# Keyboard.net
KiCad netlist of a schematic drawn in EasyEDA Pro
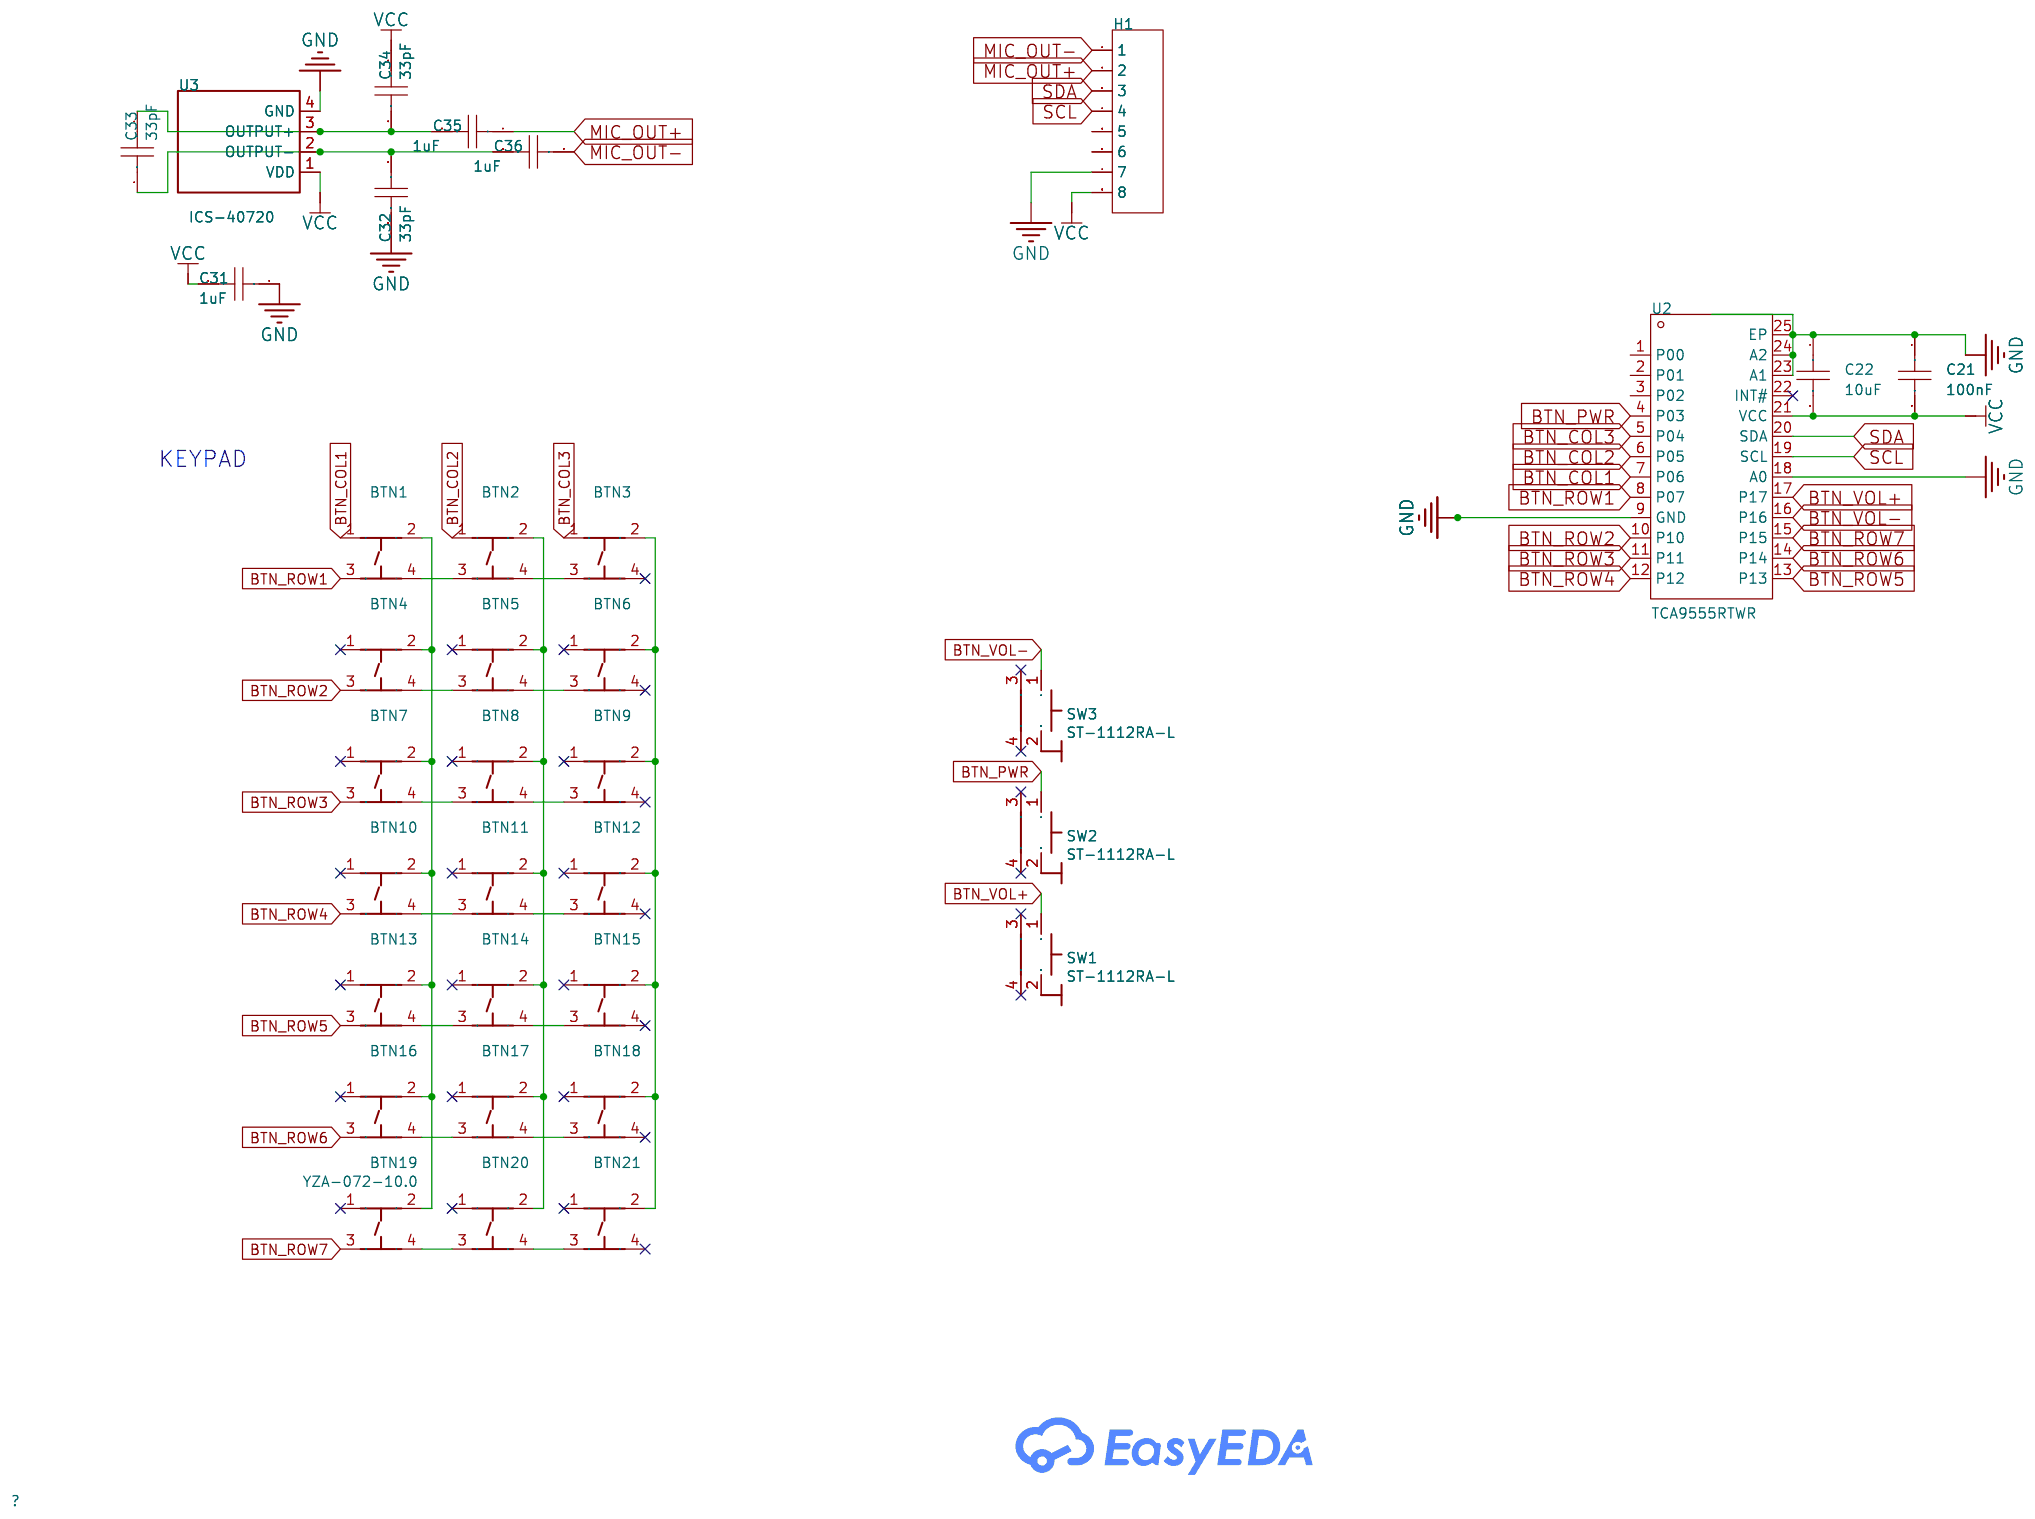
[diagram p0: schematic sheet]

(export (version "E")
  (design (tool "Eeschema 10.0.6"))
  (components
    (comp (ref "BTN1")
      (value "YZA-072-10.0")
      (footprint "easyedapro:SW-SMD_4P-L6.0-W6.0-P4.5-LS9.0-YZA-072-10.0")
      (fields (field (name "Manufacturer") "YIZHI(逸致)") (field (name "Contributor") "lcsc"))
      (libsource (lib "easyedapro") (part "YZA-072-10.0"))
    )
    (comp (ref "BTN2")
      (value "YZA-072-10.0")
      (footprint "easyedapro:SW-SMD_4P-L6.0-W6.0-P4.5-LS9.0-YZA-072-10.0")
      (fields (field (name "Manufacturer") "YIZHI(逸致)") (field (name "Contributor") "lcsc"))
      (libsource (lib "easyedapro") (part "YZA-072-10.0"))
    )
    (comp (ref "BTN3")
      (value "YZA-072-10.0")
      (footprint "easyedapro:SW-SMD_4P-L6.0-W6.0-P4.5-LS9.0-YZA-072-10.0")
      (fields (field (name "Manufacturer") "YIZHI(逸致)") (field (name "Contributor") "lcsc"))
      (libsource (lib "easyedapro") (part "YZA-072-10.0"))
    )
    (comp (ref "BTN4")
      (value "YZA-072-10.0")
      (footprint "easyedapro:SW-SMD_4P-L6.0-W6.0-P4.5-LS9.0-YZA-072-10.0")
      (fields (field (name "Manufacturer") "YIZHI(逸致)") (field (name "Contributor") "lcsc"))
      (libsource (lib "easyedapro") (part "YZA-072-10.0"))
    )
    (comp (ref "BTN5")
      (value "YZA-072-10.0")
      (footprint "easyedapro:SW-SMD_4P-L6.0-W6.0-P4.5-LS9.0-YZA-072-10.0")
      (fields (field (name "Manufacturer") "YIZHI(逸致)") (field (name "Contributor") "lcsc"))
      (libsource (lib "easyedapro") (part "YZA-072-10.0"))
    )
    (comp (ref "BTN6")
      (value "YZA-072-10.0")
      (footprint "easyedapro:SW-SMD_4P-L6.0-W6.0-P4.5-LS9.0-YZA-072-10.0")
      (fields (field (name "Manufacturer") "YIZHI(逸致)") (field (name "Contributor") "lcsc"))
      (libsource (lib "easyedapro") (part "YZA-072-10.0"))
    )
    (comp (ref "BTN7")
      (value "YZA-072-10.0")
      (footprint "easyedapro:SW-SMD_4P-L6.0-W6.0-P4.5-LS9.0-YZA-072-10.0")
      (fields (field (name "Manufacturer") "YIZHI(逸致)") (field (name "Contributor") "lcsc"))
      (libsource (lib "easyedapro") (part "YZA-072-10.0"))
    )
    (comp (ref "BTN8")
      (value "YZA-072-10.0")
      (footprint "easyedapro:SW-SMD_4P-L6.0-W6.0-P4.5-LS9.0-YZA-072-10.0")
      (fields (field (name "Manufacturer") "YIZHI(逸致)") (field (name "Contributor") "lcsc"))
      (libsource (lib "easyedapro") (part "YZA-072-10.0"))
    )
    (comp (ref "BTN9")
      (value "YZA-072-10.0")
      (footprint "easyedapro:SW-SMD_4P-L6.0-W6.0-P4.5-LS9.0-YZA-072-10.0")
      (fields (field (name "Manufacturer") "YIZHI(逸致)") (field (name "Contributor") "lcsc"))
      (libsource (lib "easyedapro") (part "YZA-072-10.0"))
    )
    (comp (ref "BTN10")
      (value "YZA-072-10.0")
      (footprint "easyedapro:SW-SMD_4P-L6.0-W6.0-P4.5-LS9.0-YZA-072-10.0")
      (fields (field (name "Manufacturer") "YIZHI(逸致)") (field (name "Contributor") "lcsc"))
      (libsource (lib "easyedapro") (part "YZA-072-10.0"))
    )
    (comp (ref "BTN11")
      (value "YZA-072-10.0")
      (footprint "easyedapro:SW-SMD_4P-L6.0-W6.0-P4.5-LS9.0-YZA-072-10.0")
      (fields (field (name "Manufacturer") "YIZHI(逸致)") (field (name "Contributor") "lcsc"))
      (libsource (lib "easyedapro") (part "YZA-072-10.0"))
    )
    (comp (ref "BTN12")
      (value "YZA-072-10.0")
      (footprint "easyedapro:SW-SMD_4P-L6.0-W6.0-P4.5-LS9.0-YZA-072-10.0")
      (fields (field (name "Manufacturer") "YIZHI(逸致)") (field (name "Contributor") "lcsc"))
      (libsource (lib "easyedapro") (part "YZA-072-10.0"))
    )
    (comp (ref "BTN13")
      (value "YZA-072-10.0")
      (footprint "easyedapro:SW-SMD_4P-L6.0-W6.0-P4.5-LS9.0-YZA-072-10.0")
      (fields (field (name "Manufacturer") "YIZHI(逸致)") (field (name "Contributor") "lcsc"))
      (libsource (lib "easyedapro") (part "YZA-072-10.0"))
    )
    (comp (ref "BTN14")
      (value "YZA-072-10.0")
      (footprint "easyedapro:SW-SMD_4P-L6.0-W6.0-P4.5-LS9.0-YZA-072-10.0")
      (fields (field (name "Manufacturer") "YIZHI(逸致)") (field (name "Contributor") "lcsc"))
      (libsource (lib "easyedapro") (part "YZA-072-10.0"))
    )
    (comp (ref "BTN15")
      (value "YZA-072-10.0")
      (footprint "easyedapro:SW-SMD_4P-L6.0-W6.0-P4.5-LS9.0-YZA-072-10.0")
      (fields (field (name "Manufacturer") "YIZHI(逸致)") (field (name "Contributor") "lcsc"))
      (libsource (lib "easyedapro") (part "YZA-072-10.0"))
    )
    (comp (ref "BTN16")
      (value "YZA-072-10.0")
      (footprint "easyedapro:SW-SMD_4P-L6.0-W6.0-P4.5-LS9.0-YZA-072-10.0")
      (fields (field (name "Manufacturer") "YIZHI(逸致)") (field (name "Contributor") "lcsc"))
      (libsource (lib "easyedapro") (part "YZA-072-10.0"))
    )
    (comp (ref "BTN17")
      (value "YZA-072-10.0")
      (footprint "easyedapro:SW-SMD_4P-L6.0-W6.0-P4.5-LS9.0-YZA-072-10.0")
      (fields (field (name "Manufacturer") "YIZHI(逸致)") (field (name "Contributor") "lcsc"))
      (libsource (lib "easyedapro") (part "YZA-072-10.0"))
    )
    (comp (ref "BTN18")
      (value "YZA-072-10.0")
      (footprint "easyedapro:SW-SMD_4P-L6.0-W6.0-P4.5-LS9.0-YZA-072-10.0")
      (fields (field (name "Manufacturer") "YIZHI(逸致)") (field (name "Contributor") "lcsc"))
      (libsource (lib "easyedapro") (part "YZA-072-10.0"))
    )
    (comp (ref "BTN19")
      (value "YZA-072-10.0")
      (footprint "easyedapro:SW-SMD_4P-L6.0-W6.0-P4.5-LS9.0-YZA-072-10.0")
      (fields (field (name "Manufacturer") "YIZHI(逸致)") (field (name "Contributor") "lcsc"))
      (libsource (lib "easyedapro") (part "YZA-072-10.0"))
    )
    (comp (ref "BTN20")
      (value "YZA-072-10.0")
      (footprint "easyedapro:SW-SMD_4P-L6.0-W6.0-P4.5-LS9.0-YZA-072-10.0")
      (fields (field (name "Manufacturer") "YIZHI(逸致)") (field (name "Contributor") "lcsc"))
      (libsource (lib "easyedapro") (part "YZA-072-10.0"))
    )
    (comp (ref "BTN21")
      (value "YZA-072-10.0")
      (footprint "easyedapro:SW-SMD_4P-L6.0-W6.0-P4.5-LS9.0-YZA-072-10.0")
      (fields (field (name "Manufacturer") "YIZHI(逸致)") (field (name "Contributor") "lcsc"))
      (libsource (lib "easyedapro") (part "YZA-072-10.0"))
    )
    (comp (ref "C21")
      (value "100nF")
      (footprint "easyedapro:C0603")
      (libsource (lib "easyedapro") (part "CAP"))
    )
    (comp (ref "C22")
      (value "10uF")
      (footprint "easyedapro:C0603")
      (libsource (lib "easyedapro") (part "CAP"))
    )
    (comp (ref "C31")
      (value "1uF")
      (footprint "easyedapro:C0603")
      (libsource (lib "easyedapro") (part "CAP"))
    )
    (comp (ref "C32")
      (value "33pF")
      (footprint "easyedapro:C0603")
      (libsource (lib "easyedapro") (part "CAP"))
    )
    (comp (ref "C33")
      (value "33pF")
      (footprint "easyedapro:C0603")
      (libsource (lib "easyedapro") (part "CAP"))
    )
    (comp (ref "C34")
      (value "33pF")
      (footprint "easyedapro:C0603")
      (libsource (lib "easyedapro") (part "CAP"))
    )
    (comp (ref "C35")
      (value "1uF")
      (footprint "easyedapro:C0603")
      (libsource (lib "easyedapro") (part "CAP"))
    )
    (comp (ref "C36")
      (value "1uF")
      (footprint "easyedapro:C0603")
      (libsource (lib "easyedapro") (part "CAP"))
    )
    (comp (ref "H1")
      (value "~")
      (footprint "easyedapro:HDR-TH_8P-P2.54-V-M")
      (libsource (lib "easyedapro") (part "Header-Male-2.54_1x8"))
    )
    (comp (ref "SW1")
      (value "ST-1112RA-L")
      (footprint "easyedapro:SW-SMD_ST-1112RA-L")
      (fields (field (name "Manufacturer") "RISHENG(日昇)") (field (name "Contributor") "LCSC"))
      (libsource (lib "easyedapro") (part "ST-1112RA-L"))
    )
    (comp (ref "SW2")
      (value "ST-1112RA-L")
      (footprint "easyedapro:SW-SMD_ST-1112RA-L")
      (fields (field (name "Manufacturer") "RISHENG(日昇)") (field (name "Contributor") "LCSC"))
      (libsource (lib "easyedapro") (part "ST-1112RA-L"))
    )
    (comp (ref "SW3")
      (value "ST-1112RA-L")
      (footprint "easyedapro:SW-SMD_ST-1112RA-L")
      (fields (field (name "Manufacturer") "RISHENG(日昇)") (field (name "Contributor") "LCSC"))
      (libsource (lib "easyedapro") (part "ST-1112RA-L"))
    )
    (comp (ref "U2")
      (value "TCA9555RTWR")
      (footprint "easyedapro:VFQFPN-24_L4.0-W4.0-P0.50-BL-EP2.8")
      (fields (field (name "Manufacturer") "TI(德州仪器)"))
      (libsource (lib "easyedapro") (part "TCA9555RTWR"))
    )
    (comp (ref "U3")
      (value "ICS-40720")
      (footprint "easyedapro:SMD_4P-P0.88_ICS-40720")
      (fields (field (name "Manufacturer") "TDK InvenSense(应美盛)") (field (name "Contributor") "lcsc"))
      (libsource (lib "easyedapro") (part "ICS-40720"))
    )
  )
  (nets
    (net (code "1") (name "BTN_COL1") (class "Default")
      (node (ref "BTN1") (pin "1") (pinfunction "1_1") (pintype "unspecified"))
      (node (ref "U2") (pin "7") (pinfunction "P06_7") (pintype "unspecified"))
    )
    (net (code "2") (name "BTN_COL2") (class "Default")
      (node (ref "BTN2") (pin "1") (pinfunction "1_1") (pintype "unspecified"))
      (node (ref "U2") (pin "6") (pinfunction "P05_6") (pintype "unspecified"))
    )
    (net (code "3") (name "BTN_COL3") (class "Default")
      (node (ref "BTN3") (pin "1") (pinfunction "1_1") (pintype "unspecified"))
      (node (ref "U2") (pin "5") (pinfunction "P04_5") (pintype "unspecified"))
    )
    (net (code "4") (name "BTN_PWR") (class "Default")
      (node (ref "SW2") (pin "1") (pinfunction "1_1") (pintype "unspecified"))
      (node (ref "U2") (pin "4") (pinfunction "P03_4") (pintype "unspecified"))
    )
    (net (code "5") (name "BTN_ROW1") (class "Default")
      (node (ref "BTN1") (pin "3") (pinfunction "3_3") (pintype "unspecified"))
      (node (ref "U2") (pin "8") (pinfunction "P07_8") (pintype "unspecified"))
    )
    (net (code "6") (name "BTN_ROW2") (class "Default")
      (node (ref "BTN4") (pin "3") (pinfunction "3_3") (pintype "unspecified"))
      (node (ref "U2") (pin "10") (pinfunction "P10_10") (pintype "unspecified"))
    )
    (net (code "7") (name "BTN_ROW3") (class "Default")
      (node (ref "BTN7") (pin "3") (pinfunction "3_3") (pintype "unspecified"))
      (node (ref "U2") (pin "11") (pinfunction "P11_11") (pintype "unspecified"))
    )
    (net (code "8") (name "BTN_ROW4") (class "Default")
      (node (ref "BTN10") (pin "3") (pinfunction "3_3") (pintype "unspecified"))
      (node (ref "U2") (pin "12") (pinfunction "P12_12") (pintype "unspecified"))
    )
    (net (code "9") (name "BTN_ROW5") (class "Default")
      (node (ref "BTN13") (pin "3") (pinfunction "3_3") (pintype "unspecified"))
      (node (ref "U2") (pin "13") (pinfunction "P13_13") (pintype "unspecified"))
    )
    (net (code "10") (name "BTN_ROW6") (class "Default")
      (node (ref "BTN16") (pin "3") (pinfunction "3_3") (pintype "unspecified"))
      (node (ref "U2") (pin "14") (pinfunction "P14_14") (pintype "unspecified"))
    )
    (net (code "11") (name "BTN_ROW7") (class "Default")
      (node (ref "BTN19") (pin "3") (pinfunction "3_3") (pintype "unspecified"))
      (node (ref "U2") (pin "15") (pinfunction "P15_15") (pintype "unspecified"))
    )
    (net (code "12") (name "BTN_VOL+") (class "Default")
      (node (ref "SW1") (pin "1") (pinfunction "1_1") (pintype "unspecified"))
      (node (ref "U2") (pin "17") (pinfunction "P17_17") (pintype "unspecified"))
    )
    (net (code "13") (name "BTN_VOL-") (class "Default")
      (node (ref "SW3") (pin "1") (pinfunction "1_1") (pintype "unspecified"))
      (node (ref "U2") (pin "16") (pinfunction "P16_16") (pintype "unspecified"))
    )
    (net (code "14") (name "GND") (class "Default")
      (node (ref "C21") (pin "1") (pinfunction "1_1") (pintype "input"))
      (node (ref "C22") (pin "1") (pinfunction "1_1") (pintype "input"))
      (node (ref "C31") (pin "1") (pinfunction "1_1") (pintype "input"))
      (node (ref "C32") (pin "2") (pinfunction "2_2") (pintype "input"))
      (node (ref "H1") (pin "7") (pinfunction "7_7") (pintype "unspecified"))
      (node (ref "U2") (pin "18") (pinfunction "A0_18") (pintype "unspecified"))
      (node (ref "U2") (pin "23") (pinfunction "A1_23") (pintype "unspecified"))
      (node (ref "U2") (pin "24") (pinfunction "A2_24") (pintype "unspecified"))
      (node (ref "U2") (pin "25") (pinfunction "EP_25") (pintype "unspecified"))
      (node (ref "U2") (pin "9") (pinfunction "GND_9") (pintype "unspecified"))
      (node (ref "U3") (pin "4") (pinfunction "GND_4") (pintype "unspecified"))
    )
    (net (code "15") (name "MIC_OUT+") (class "Default")
      (node (ref "C35") (pin "1") (pinfunction "1_1") (pintype "input"))
      (node (ref "H1") (pin "2") (pinfunction "2_2") (pintype "unspecified"))
    )
    (net (code "16") (name "MIC_OUT-") (class "Default")
      (node (ref "C36") (pin "1") (pinfunction "1_1") (pintype "input"))
      (node (ref "H1") (pin "1") (pinfunction "1_1") (pintype "unspecified"))
    )
    (net (code "17") (name "Net-(BTN1-Pad2)") (class "Default")
      (node (ref "BTN1") (pin "2") (pinfunction "2_2") (pintype "unspecified"))
      (node (ref "BTN10") (pin "2") (pinfunction "2_2") (pintype "unspecified"))
      (node (ref "BTN13") (pin "2") (pinfunction "2_2") (pintype "unspecified"))
      (node (ref "BTN16") (pin "2") (pinfunction "2_2") (pintype "unspecified"))
      (node (ref "BTN19") (pin "2") (pinfunction "2_2") (pintype "unspecified"))
      (node (ref "BTN4") (pin "2") (pinfunction "2_2") (pintype "unspecified"))
      (node (ref "BTN7") (pin "2") (pinfunction "2_2") (pintype "unspecified"))
    )
    (net (code "18") (name "Net-(BTN1-Pad4)") (class "Default")
      (node (ref "BTN1") (pin "4") (pinfunction "4_4") (pintype "unspecified"))
      (node (ref "BTN2") (pin "3") (pinfunction "3_3") (pintype "unspecified"))
    )
    (net (code "19") (name "Net-(BTN2-Pad4)") (class "Default")
      (node (ref "BTN2") (pin "4") (pinfunction "4_4") (pintype "unspecified"))
      (node (ref "BTN3") (pin "3") (pinfunction "3_3") (pintype "unspecified"))
    )
    (net (code "20") (name "Net-(BTN4-Pad4)") (class "Default")
      (node (ref "BTN4") (pin "4") (pinfunction "4_4") (pintype "unspecified"))
      (node (ref "BTN5") (pin "3") (pinfunction "3_3") (pintype "unspecified"))
    )
    (net (code "21") (name "Net-(BTN5-Pad4)") (class "Default")
      (node (ref "BTN5") (pin "4") (pinfunction "4_4") (pintype "unspecified"))
      (node (ref "BTN6") (pin "3") (pinfunction "3_3") (pintype "unspecified"))
    )
    (net (code "22") (name "Net-(BTN7-Pad4)") (class "Default")
      (node (ref "BTN7") (pin "4") (pinfunction "4_4") (pintype "unspecified"))
      (node (ref "BTN8") (pin "3") (pinfunction "3_3") (pintype "unspecified"))
    )
    (net (code "23") (name "Net-(BTN8-Pad4)") (class "Default")
      (node (ref "BTN8") (pin "4") (pinfunction "4_4") (pintype "unspecified"))
      (node (ref "BTN9") (pin "3") (pinfunction "3_3") (pintype "unspecified"))
    )
    (net (code "24") (name "Net-(BTN10-Pad4)") (class "Default")
      (node (ref "BTN10") (pin "4") (pinfunction "4_4") (pintype "unspecified"))
      (node (ref "BTN11") (pin "3") (pinfunction "3_3") (pintype "unspecified"))
    )
    (net (code "25") (name "Net-(BTN11-Pad2)") (class "Default")
      (node (ref "BTN11") (pin "2") (pinfunction "2_2") (pintype "unspecified"))
      (node (ref "BTN14") (pin "2") (pinfunction "2_2") (pintype "unspecified"))
      (node (ref "BTN17") (pin "2") (pinfunction "2_2") (pintype "unspecified"))
      (node (ref "BTN2") (pin "2") (pinfunction "2_2") (pintype "unspecified"))
      (node (ref "BTN20") (pin "2") (pinfunction "2_2") (pintype "unspecified"))
      (node (ref "BTN5") (pin "2") (pinfunction "2_2") (pintype "unspecified"))
      (node (ref "BTN8") (pin "2") (pinfunction "2_2") (pintype "unspecified"))
    )
    (net (code "26") (name "Net-(BTN11-Pad4)") (class "Default")
      (node (ref "BTN11") (pin "4") (pinfunction "4_4") (pintype "unspecified"))
      (node (ref "BTN12") (pin "3") (pinfunction "3_3") (pintype "unspecified"))
    )
    (net (code "27") (name "Net-(BTN12-Pad2)") (class "Default")
      (node (ref "BTN12") (pin "2") (pinfunction "2_2") (pintype "unspecified"))
      (node (ref "BTN15") (pin "2") (pinfunction "2_2") (pintype "unspecified"))
      (node (ref "BTN18") (pin "2") (pinfunction "2_2") (pintype "unspecified"))
      (node (ref "BTN21") (pin "2") (pinfunction "2_2") (pintype "unspecified"))
      (node (ref "BTN3") (pin "2") (pinfunction "2_2") (pintype "unspecified"))
      (node (ref "BTN6") (pin "2") (pinfunction "2_2") (pintype "unspecified"))
      (node (ref "BTN9") (pin "2") (pinfunction "2_2") (pintype "unspecified"))
    )
    (net (code "28") (name "Net-(BTN13-Pad4)") (class "Default")
      (node (ref "BTN13") (pin "4") (pinfunction "4_4") (pintype "unspecified"))
      (node (ref "BTN14") (pin "3") (pinfunction "3_3") (pintype "unspecified"))
    )
    (net (code "29") (name "Net-(BTN14-Pad4)") (class "Default")
      (node (ref "BTN14") (pin "4") (pinfunction "4_4") (pintype "unspecified"))
      (node (ref "BTN15") (pin "3") (pinfunction "3_3") (pintype "unspecified"))
    )
    (net (code "30") (name "Net-(BTN16-Pad4)") (class "Default")
      (node (ref "BTN16") (pin "4") (pinfunction "4_4") (pintype "unspecified"))
      (node (ref "BTN17") (pin "3") (pinfunction "3_3") (pintype "unspecified"))
    )
    (net (code "31") (name "Net-(BTN17-Pad4)") (class "Default")
      (node (ref "BTN17") (pin "4") (pinfunction "4_4") (pintype "unspecified"))
      (node (ref "BTN18") (pin "3") (pinfunction "3_3") (pintype "unspecified"))
    )
    (net (code "32") (name "Net-(BTN19-Pad4)") (class "Default")
      (node (ref "BTN19") (pin "4") (pinfunction "4_4") (pintype "unspecified"))
      (node (ref "BTN20") (pin "3") (pinfunction "3_3") (pintype "unspecified"))
    )
    (net (code "33") (name "Net-(BTN20-Pad4)") (class "Default")
      (node (ref "BTN20") (pin "4") (pinfunction "4_4") (pintype "unspecified"))
      (node (ref "BTN21") (pin "3") (pinfunction "3_3") (pintype "unspecified"))
    )
    (net (code "34") (name "Net-(U3-OUTPUT+)") (class "Default")
      (node (ref "C33") (pin "1") (pinfunction "1_1") (pintype "input"))
      (node (ref "C34") (pin "2") (pinfunction "2_2") (pintype "input"))
      (node (ref "C35") (pin "2") (pinfunction "2_2") (pintype "input"))
      (node (ref "U3") (pin "3") (pinfunction "OUTPUT+_3") (pintype "unspecified"))
    )
    (net (code "35") (name "Net-(U3-OUTPUT−)") (class "Default")
      (node (ref "C32") (pin "1") (pinfunction "1_1") (pintype "input"))
      (node (ref "C33") (pin "2") (pinfunction "2_2") (pintype "input"))
      (node (ref "C36") (pin "2") (pinfunction "2_2") (pintype "input"))
      (node (ref "U3") (pin "2") (pinfunction "OUTPUT−_2") (pintype "unspecified"))
    )
    (net (code "36") (name "SCL") (class "Default")
      (node (ref "H1") (pin "4") (pinfunction "4_4") (pintype "unspecified"))
      (node (ref "U2") (pin "19") (pinfunction "SCL_19") (pintype "unspecified"))
    )
    (net (code "37") (name "SDA") (class "Default")
      (node (ref "H1") (pin "3") (pinfunction "3_3") (pintype "unspecified"))
      (node (ref "U2") (pin "20") (pinfunction "SDA_20") (pintype "unspecified"))
    )
    (net (code "38") (name "VCC") (class "Default")
      (node (ref "C21") (pin "2") (pinfunction "2_2") (pintype "input"))
      (node (ref "C22") (pin "2") (pinfunction "2_2") (pintype "input"))
      (node (ref "C31") (pin "2") (pinfunction "2_2") (pintype "input"))
      (node (ref "C34") (pin "1") (pinfunction "1_1") (pintype "input"))
      (node (ref "H1") (pin "8") (pinfunction "8_8") (pintype "unspecified"))
      (node (ref "SW1") (pin "2") (pinfunction "2_2") (pintype "unspecified"))
      (node (ref "SW2") (pin "2") (pinfunction "2_2") (pintype "unspecified"))
      (node (ref "SW3") (pin "2") (pinfunction "2_2") (pintype "unspecified"))
      (node (ref "U2") (pin "21") (pinfunction "VCC_21") (pintype "unspecified"))
      (node (ref "U3") (pin "1") (pinfunction "VDD_1") (pintype "unspecified"))
    )
    (net (code "39") (name "unconnected-(BTN3-Pad4)") (class "Default")
      (node (ref "BTN3") (pin "4") (pinfunction "4_4") (pintype "unspecified+no_connect"))
    )
    (net (code "40") (name "unconnected-(BTN4-Pad1)") (class "Default")
      (node (ref "BTN4") (pin "1") (pinfunction "1_1") (pintype "unspecified+no_connect"))
    )
    (net (code "41") (name "unconnected-(BTN5-Pad1)") (class "Default")
      (node (ref "BTN5") (pin "1") (pinfunction "1_1") (pintype "unspecified+no_connect"))
    )
    (net (code "42") (name "unconnected-(BTN6-Pad1)") (class "Default")
      (node (ref "BTN6") (pin "1") (pinfunction "1_1") (pintype "unspecified+no_connect"))
    )
    (net (code "43") (name "unconnected-(BTN6-Pad4)") (class "Default")
      (node (ref "BTN6") (pin "4") (pinfunction "4_4") (pintype "unspecified+no_connect"))
    )
    (net (code "44") (name "unconnected-(BTN7-Pad1)") (class "Default")
      (node (ref "BTN7") (pin "1") (pinfunction "1_1") (pintype "unspecified+no_connect"))
    )
    (net (code "45") (name "unconnected-(BTN8-Pad1)") (class "Default")
      (node (ref "BTN8") (pin "1") (pinfunction "1_1") (pintype "unspecified+no_connect"))
    )
    (net (code "46") (name "unconnected-(BTN9-Pad1)") (class "Default")
      (node (ref "BTN9") (pin "1") (pinfunction "1_1") (pintype "unspecified+no_connect"))
    )
    (net (code "47") (name "unconnected-(BTN9-Pad4)") (class "Default")
      (node (ref "BTN9") (pin "4") (pinfunction "4_4") (pintype "unspecified+no_connect"))
    )
    (net (code "48") (name "unconnected-(BTN10-Pad1)") (class "Default")
      (node (ref "BTN10") (pin "1") (pinfunction "1_1") (pintype "unspecified+no_connect"))
    )
    (net (code "49") (name "unconnected-(BTN11-Pad1)") (class "Default")
      (node (ref "BTN11") (pin "1") (pinfunction "1_1") (pintype "unspecified+no_connect"))
    )
    (net (code "50") (name "unconnected-(BTN12-Pad1)") (class "Default")
      (node (ref "BTN12") (pin "1") (pinfunction "1_1") (pintype "unspecified+no_connect"))
    )
    (net (code "51") (name "unconnected-(BTN12-Pad4)") (class "Default")
      (node (ref "BTN12") (pin "4") (pinfunction "4_4") (pintype "unspecified+no_connect"))
    )
    (net (code "52") (name "unconnected-(BTN13-Pad1)") (class "Default")
      (node (ref "BTN13") (pin "1") (pinfunction "1_1") (pintype "unspecified+no_connect"))
    )
    (net (code "53") (name "unconnected-(BTN14-Pad1)") (class "Default")
      (node (ref "BTN14") (pin "1") (pinfunction "1_1") (pintype "unspecified+no_connect"))
    )
    (net (code "54") (name "unconnected-(BTN15-Pad1)") (class "Default")
      (node (ref "BTN15") (pin "1") (pinfunction "1_1") (pintype "unspecified+no_connect"))
    )
    (net (code "55") (name "unconnected-(BTN15-Pad4)") (class "Default")
      (node (ref "BTN15") (pin "4") (pinfunction "4_4") (pintype "unspecified+no_connect"))
    )
    (net (code "56") (name "unconnected-(BTN16-Pad1)") (class "Default")
      (node (ref "BTN16") (pin "1") (pinfunction "1_1") (pintype "unspecified+no_connect"))
    )
    (net (code "57") (name "unconnected-(BTN17-Pad1)") (class "Default")
      (node (ref "BTN17") (pin "1") (pinfunction "1_1") (pintype "unspecified+no_connect"))
    )
    (net (code "58") (name "unconnected-(BTN18-Pad1)") (class "Default")
      (node (ref "BTN18") (pin "1") (pinfunction "1_1") (pintype "unspecified+no_connect"))
    )
    (net (code "59") (name "unconnected-(BTN18-Pad4)") (class "Default")
      (node (ref "BTN18") (pin "4") (pinfunction "4_4") (pintype "unspecified+no_connect"))
    )
    (net (code "60") (name "unconnected-(BTN19-Pad1)") (class "Default")
      (node (ref "BTN19") (pin "1") (pinfunction "1_1") (pintype "unspecified+no_connect"))
    )
    (net (code "61") (name "unconnected-(BTN20-Pad1)") (class "Default")
      (node (ref "BTN20") (pin "1") (pinfunction "1_1") (pintype "unspecified+no_connect"))
    )
    (net (code "62") (name "unconnected-(BTN21-Pad1)") (class "Default")
      (node (ref "BTN21") (pin "1") (pinfunction "1_1") (pintype "unspecified+no_connect"))
    )
    (net (code "63") (name "unconnected-(BTN21-Pad4)") (class "Default")
      (node (ref "BTN21") (pin "4") (pinfunction "4_4") (pintype "unspecified+no_connect"))
    )
    (net (code "64") (name "unconnected-(H1-Pad5)") (class "Default")
      (node (ref "H1") (pin "5") (pinfunction "5_5") (pintype "unspecified"))
    )
    (net (code "65") (name "unconnected-(H1-Pad6)") (class "Default")
      (node (ref "H1") (pin "6") (pinfunction "6_6") (pintype "unspecified"))
    )
    (net (code "66") (name "unconnected-(SW1-Pad3)") (class "Default")
      (node (ref "SW1") (pin "3") (pinfunction "3_3") (pintype "unspecified+no_connect"))
    )
    (net (code "67") (name "unconnected-(SW1-Pad4)") (class "Default")
      (node (ref "SW1") (pin "4") (pinfunction "4_4") (pintype "unspecified+no_connect"))
    )
    (net (code "68") (name "unconnected-(SW2-Pad3)") (class "Default")
      (node (ref "SW2") (pin "3") (pinfunction "3_3") (pintype "unspecified+no_connect"))
    )
    (net (code "69") (name "unconnected-(SW2-Pad4)") (class "Default")
      (node (ref "SW2") (pin "4") (pinfunction "4_4") (pintype "unspecified+no_connect"))
    )
    (net (code "70") (name "unconnected-(SW3-Pad3)") (class "Default")
      (node (ref "SW3") (pin "3") (pinfunction "3_3") (pintype "unspecified+no_connect"))
    )
    (net (code "71") (name "unconnected-(SW3-Pad4)") (class "Default")
      (node (ref "SW3") (pin "4") (pinfunction "4_4") (pintype "unspecified+no_connect"))
    )
    (net (code "72") (name "unconnected-(U2-INT#-Pad22)") (class "Default")
      (node (ref "U2") (pin "22") (pinfunction "INT#_22") (pintype "unspecified+no_connect"))
    )
    (net (code "73") (name "unconnected-(U2-P00-Pad1)") (class "Default")
      (node (ref "U2") (pin "1") (pinfunction "P00_1") (pintype "unspecified"))
    )
    (net (code "74") (name "unconnected-(U2-P01-Pad2)") (class "Default")
      (node (ref "U2") (pin "2") (pinfunction "P01_2") (pintype "unspecified"))
    )
    (net (code "75") (name "unconnected-(U2-P02-Pad3)") (class "Default")
      (node (ref "U2") (pin "3") (pinfunction "P02_3") (pintype "unspecified"))
    )
  )
)
